# BUCK_5v_TPS5430.net
KiCad netlist of a schematic drawn in Altium Designer
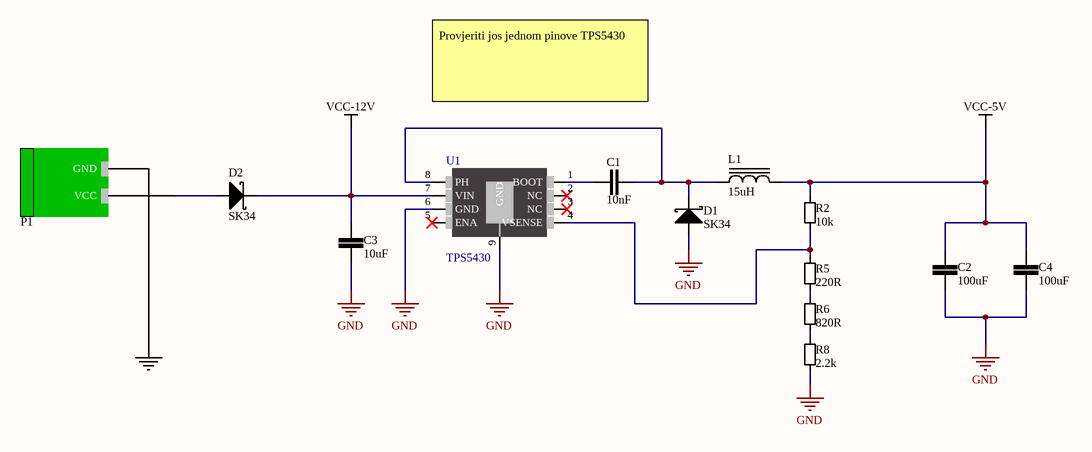
[diagram p0: BUCK_5v_TPS5430.SchDoc]

(export (version "E")
  (design (tool "Eeschema 10.0.6"))
  (components
    (comp (ref "C1")
      (value "10nF")
      (footprint "CER_0805")
      (description "CAP CER 10n 50V X7R 10% 0805")
      (fields (field (name "LCSC PART #") "C1710"))
      (libsource (lib "Capacitors") (part "CER 10n 50V X7R"))
    )
    (comp (ref "C2")
      (value "100uF")
      (footprint "CER_1210")
      (description "CAP CER 100u X5R 6.3V 10% 1210")
      (libsource (lib "Capacitors") (part "00002108"))
    )
    (comp (ref "C3")
      (value "10uF")
      (footprint "CER_0805")
      (description "CAP CER 10u 25V X5R 10% 0805")
      (fields (field (name "LCSC PART #") "C15850"))
      (libsource (lib "Capacitors") (part "CER 10u 25V X5R"))
    )
    (comp (ref "C4")
      (value "100uF")
      (footprint "CER_1210")
      (description "CAP CER 100u X5R 6.3V 10% 1210")
      (libsource (lib "Capacitors") (part "00002108"))
    )
    (comp (ref "D1")
      (value "SK34")
      (footprint "DO214AC")
      (description "DIODE SCHOTTKY 40V 3A DO214AC")
      (fields (field (name "MANUFACTURER") "Vishay Semiconductor Diodes Division"))
      (libsource (lib "Discrete_Semiconductor") (part "SK34"))
    )
    (comp (ref "D2")
      (value "SK34")
      (footprint "DO214AC")
      (description "DIODE SCHOTTKY 40V 3A DO214AC")
      (fields (field (name "MANUFACTURER") "Vishay Semiconductor Diodes Division"))
      (libsource (lib "Discrete_Semiconductor") (part "SK34"))
    )
    (comp (ref "L1")
      (value "15uH")
      (footprint "INDUCTOR_SS1260-103MLD")
      (description "FIXED IND 15uH 3A")
      (libsource (lib "Discrete_Semiconductor") (part "IND_15uH"))
    )
    (comp (ref "P1")
      (value "2EDGRC-5.08-02P-14-00A(H)")
      (footprint "PWR_Con")
      (description "TERM BLOCK HDR 2POS 90DEG 5.08MM")
      (libsource (lib "Electro_Mechanical") (part "00000002"))
    )
    (comp (ref "R2")
      (value "10k")
      (footprint "RESC2013X38N-0805-NOOVERLAY")
      (description "RES SMD 10 kOhm 1/8W 0805")
      (libsource (lib "Resistors") (part "000001002"))
    )
    (comp (ref "R5")
      (value "220R")
      (footprint "RESC2013X38N-0805-NOOVERLAY")
      (description "RES SMD 220 Ohm 1/8W 0805")
      (fields (field (name "LCSC PART #") "C17557"))
      (libsource (lib "Resistors") (part "RES SMD 220 Ohm 0805"))
    )
    (comp (ref "R6")
      (value "820R")
      (footprint "RESC2013X38N-0805-NOOVERLAY")
      (description "RES SMD 820 Ohm 1/8W 0805")
      (fields (field (name "LCSC PART #") "C17837"))
      (libsource (lib "Resistors") (part "RES SMD 820 Ohm 0805"))
    )
    (comp (ref "R8")
      (value "2.2k")
      (footprint "RESC2013X38N-0805-NOOVERLAY")
      (description "RES SMD 2.2 kOhm 1/8W 0805")
      (fields (field (name "LCSC PART #") "C17520"))
      (libsource (lib "Resistors") (part "RES SMD 2.2 kOhm 0805"))
    )
    (comp (ref "U1")
      (value "TPS5430")
      (footprint "HSOP-8")
      (description "IC REG BUCK ADJ 3A 8SOPWRPAD")
      (fields (field (name "LCSC PART #") "C9864"))
      (libsource (lib "Integrated_circuits") (part "TPS5430"))
    )
  )
  (nets
    (net (code "1") (name "GND") (class "Default")
      (node (ref "C2") (pin "1") (pinfunction "1_1") (pintype "passive"))
      (node (ref "C3") (pin "1") (pinfunction "1_1") (pintype "passive"))
      (node (ref "C4") (pin "1") (pinfunction "1_1") (pintype "passive"))
      (node (ref "D1") (pin "2") (pinfunction "Anode_2") (pintype "passive"))
      (node (ref "P1") (pin "1") (pinfunction "GND_1") (pintype "passive"))
      (node (ref "R8") (pin "1") (pinfunction "1_1") (pintype "passive"))
      (node (ref "U1") (pin "6") (pinfunction "GND_6") (pintype "passive"))
      (node (ref "U1") (pin "9") (pinfunction "GND_9") (pintype "passive"))
    )
    (net (code "2") (name "Net-(D1-Cathode)") (class "Default")
      (node (ref "C1") (pin "2") (pinfunction "2_2") (pintype "passive"))
      (node (ref "D1") (pin "1") (pinfunction "Cathode_1") (pintype "passive"))
      (node (ref "L1") (pin "1") (pinfunction "1_1") (pintype "passive"))
      (node (ref "U1") (pin "8") (pinfunction "PH_8") (pintype "passive"))
    )
    (net (code "3") (name "Net-(D2-Anode)") (class "Default")
      (node (ref "D2") (pin "2") (pinfunction "Anode_2") (pintype "passive"))
      (node (ref "P1") (pin "2") (pinfunction "VCC_2") (pintype "passive"))
    )
    (net (code "4") (name "Net-(R5-Pad1)") (class "Default")
      (node (ref "R5") (pin "1") (pinfunction "1_1") (pintype "passive"))
      (node (ref "R6") (pin "2") (pinfunction "2_2") (pintype "passive"))
    )
    (net (code "5") (name "Net-(R6-Pad1)") (class "Default")
      (node (ref "R6") (pin "1") (pinfunction "1_1") (pintype "passive"))
      (node (ref "R8") (pin "2") (pinfunction "2_2") (pintype "passive"))
    )
    (net (code "6") (name "Net-(U1-BOOT)") (class "Default")
      (node (ref "C1") (pin "1") (pinfunction "1_1") (pintype "passive"))
      (node (ref "U1") (pin "1") (pinfunction "BOOT_1") (pintype "passive"))
    )
    (net (code "7") (name "Net-(U1-VSENSE)") (class "Default")
      (node (ref "R2") (pin "1") (pinfunction "1_1") (pintype "passive"))
      (node (ref "R5") (pin "2") (pinfunction "2_2") (pintype "passive"))
      (node (ref "U1") (pin "4") (pinfunction "VSENSE_4") (pintype "passive"))
    )
    (net (code "8") (name "VCC-5V") (class "Default")
      (node (ref "C2") (pin "2") (pinfunction "2_2") (pintype "passive"))
      (node (ref "C4") (pin "2") (pinfunction "2_2") (pintype "passive"))
      (node (ref "L1") (pin "2") (pinfunction "2_2") (pintype "passive"))
      (node (ref "R2") (pin "2") (pinfunction "2_2") (pintype "passive"))
    )
    (net (code "9") (name "VCC-12V") (class "Default")
      (node (ref "C3") (pin "2") (pinfunction "2_2") (pintype "passive"))
      (node (ref "D2") (pin "1") (pinfunction "Cathode_1") (pintype "passive"))
      (node (ref "U1") (pin "7") (pinfunction "VIN_7") (pintype "passive"))
    )
    (net (code "10") (name "unconnected-(U1-ENA-Pad5)") (class "Default")
      (node (ref "U1") (pin "5") (pinfunction "ENA_5") (pintype "passive+no_connect"))
    )
    (net (code "11") (name "unconnected-(U1-NC-Pad2)") (class "Default")
      (node (ref "U1") (pin "2") (pinfunction "NC_2") (pintype "passive+no_connect"))
    )
    (net (code "12") (name "unconnected-(U1-NC-Pad3)") (class "Default")
      (node (ref "U1") (pin "3") (pinfunction "NC_3") (pintype "passive+no_connect"))
    )
  )
)
